# SCH_music-pad_2026-02-09.net
KiCad netlist of a schematic drawn in EasyEDA
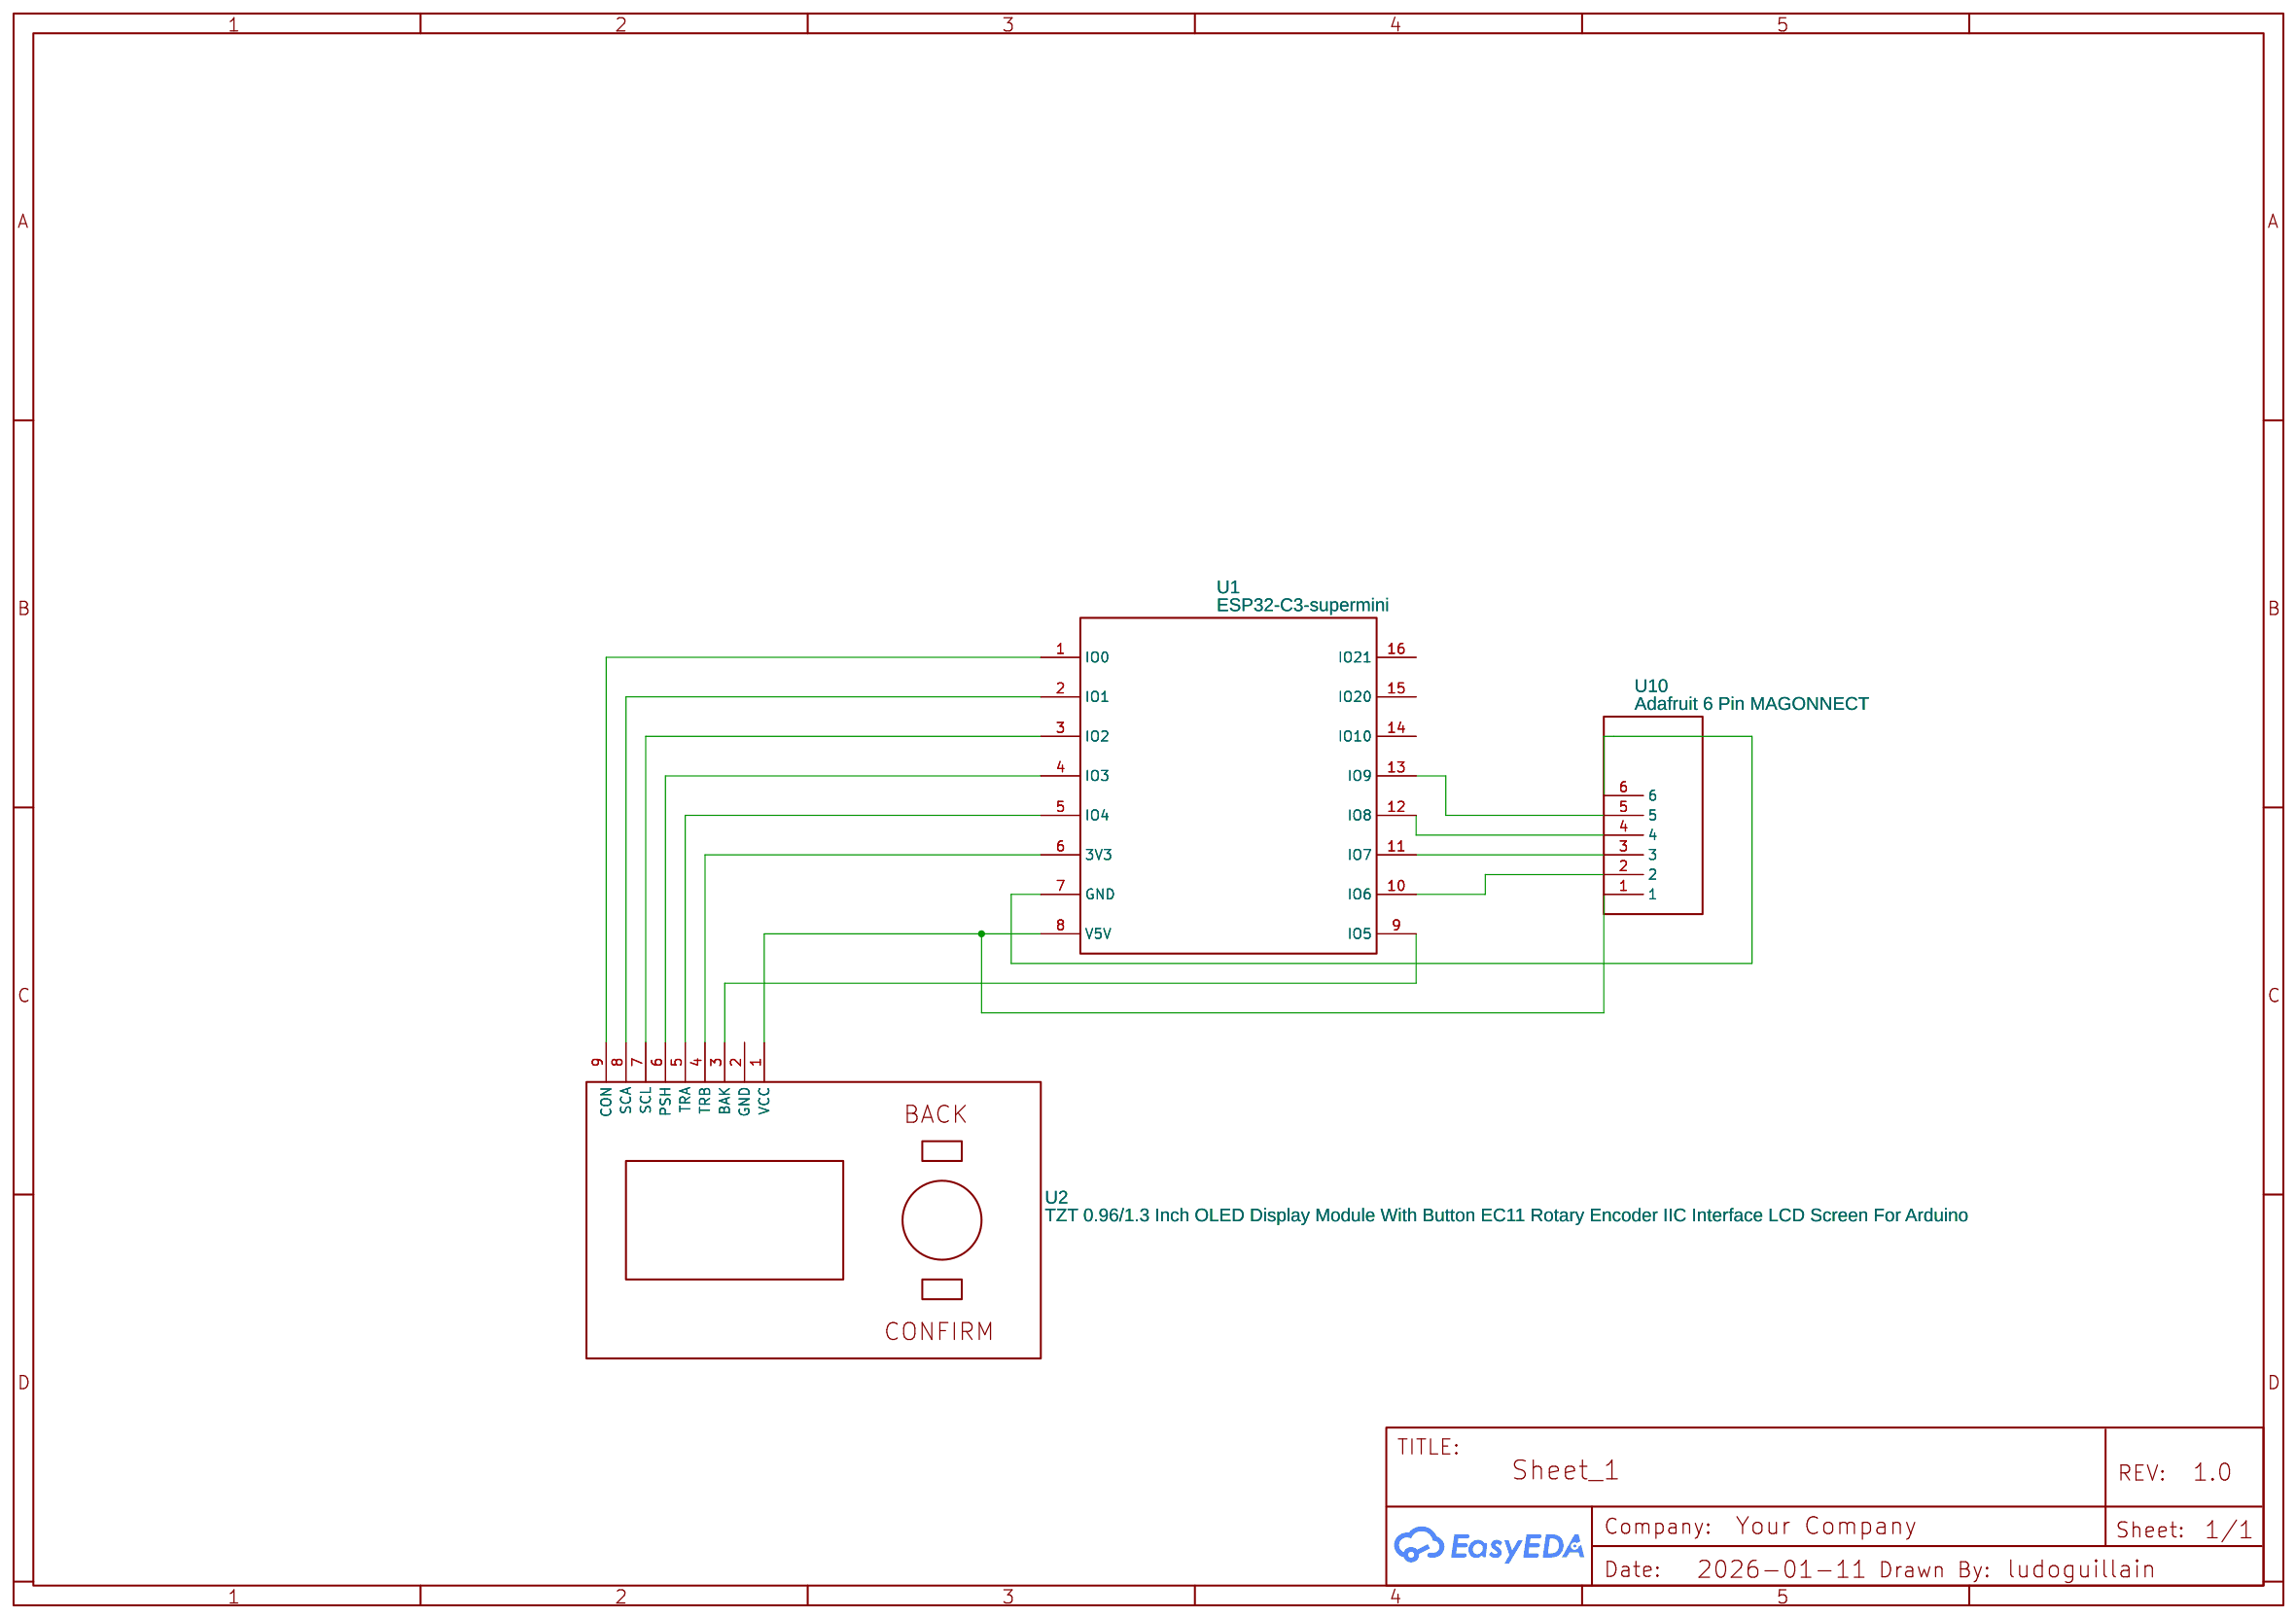
[diagram p0: schematic sheet]

(export (version "E")
  (design (tool "Eeschema 10.0.6"))
  (components
    (comp (ref "U1") (value "ESP32-C3-supermini") (libsource (lib "") (part "ESP32-C3-supermini")))
    (comp (ref "U2")
      (value "TZT 0.96/1.3 Inch OLED Display Module With Button EC11 Rotary Encoder IIC Interface LCD Screen For Arduino")
      (fields (field (name "Manufacturer Part") "8256") (field (name "Manufacturer") "TZT"))
      (libsource (lib "") (part "TZT 0.96/1.3 Inch OLED Display Module With Button EC11 Rotary Encoder IIC Interface LCD Screen For Arduino"))
    )
    (comp (ref "U10")
      (value "Adafruit 6 Pin MAGONNECT")
      (libsource (lib "") (part "Adafruit 6 Pin MAGONNECT"))
    )
  )
  (nets
    (net (code "1") (name "Net-(U1-3V3)") (class "Default")
      (node (ref "U1") (pin "6") (pinfunction "3V3_6") (pintype "unspecified"))
      (node (ref "U2") (pin "4") (pinfunction "TRB_4") (pintype "output"))
    )
    (net (code "2") (name "Net-(U1-GND)") (class "Default")
      (node (ref "U1") (pin "7") (pinfunction "GND_7") (pintype "unspecified"))
      (node (ref "U10") (pin "6") (pinfunction "6_6") (pintype "unspecified"))
    )
    (net (code "3") (name "Net-(U1-IO0)") (class "Default")
      (node (ref "U1") (pin "1") (pinfunction "IO0_1") (pintype "unspecified"))
      (node (ref "U2") (pin "9") (pinfunction "CON_9") (pintype "output"))
    )
    (net (code "4") (name "Net-(U1-IO1)") (class "Default")
      (node (ref "U1") (pin "2") (pinfunction "IO1_2") (pintype "unspecified"))
      (node (ref "U2") (pin "8") (pinfunction "SCA_8") (pintype "bidirectional"))
    )
    (net (code "5") (name "Net-(U1-IO2)") (class "Default")
      (node (ref "U1") (pin "3") (pinfunction "IO2_3") (pintype "unspecified"))
      (node (ref "U2") (pin "7") (pinfunction "SCL_7") (pintype "bidirectional"))
    )
    (net (code "6") (name "Net-(U1-IO3)") (class "Default")
      (node (ref "U1") (pin "4") (pinfunction "IO3_4") (pintype "unspecified"))
      (node (ref "U2") (pin "6") (pinfunction "PSH_6") (pintype "output"))
    )
    (net (code "7") (name "Net-(U1-IO4)") (class "Default")
      (node (ref "U1") (pin "5") (pinfunction "IO4_5") (pintype "unspecified"))
      (node (ref "U2") (pin "5") (pinfunction "TRA_5") (pintype "output"))
    )
    (net (code "8") (name "Net-(U1-IO5)") (class "Default")
      (node (ref "U1") (pin "9") (pinfunction "IO5_9") (pintype "unspecified"))
      (node (ref "U2") (pin "3") (pinfunction "BAK_3") (pintype "output"))
    )
    (net (code "9") (name "Net-(U1-IO6)") (class "Default")
      (node (ref "U1") (pin "10") (pinfunction "IO6_10") (pintype "unspecified"))
      (node (ref "U10") (pin "2") (pinfunction "2_2") (pintype "unspecified"))
    )
    (net (code "10") (name "Net-(U1-IO7)") (class "Default")
      (node (ref "U1") (pin "11") (pinfunction "IO7_11") (pintype "unspecified"))
      (node (ref "U10") (pin "3") (pinfunction "3_3") (pintype "unspecified"))
    )
    (net (code "11") (name "Net-(U1-IO8)") (class "Default")
      (node (ref "U1") (pin "12") (pinfunction "IO8_12") (pintype "unspecified"))
      (node (ref "U10") (pin "4") (pinfunction "4_4") (pintype "unspecified"))
    )
    (net (code "12") (name "Net-(U1-IO9)") (class "Default")
      (node (ref "U1") (pin "13") (pinfunction "IO9_13") (pintype "unspecified"))
      (node (ref "U10") (pin "5") (pinfunction "5_5") (pintype "unspecified"))
    )
    (net (code "13") (name "Net-(U1-V5V)") (class "Default")
      (node (ref "U1") (pin "8") (pinfunction "V5V_8") (pintype "unspecified"))
      (node (ref "U10") (pin "1") (pinfunction "1_1") (pintype "unspecified"))
      (node (ref "U2") (pin "1") (pinfunction "VCC_1") (pintype "passive"))
    )
    (net (code "14") (name "unconnected-(U1-IO10-Pad14)") (class "Default")
      (node (ref "U1") (pin "14") (pinfunction "IO10_14") (pintype "unspecified"))
    )
    (net (code "15") (name "unconnected-(U1-IO20-Pad15)") (class "Default")
      (node (ref "U1") (pin "15") (pinfunction "IO20_15") (pintype "unspecified"))
    )
    (net (code "16") (name "unconnected-(U1-IO21-Pad16)") (class "Default")
      (node (ref "U1") (pin "16") (pinfunction "IO21_16") (pintype "unspecified"))
    )
    (net (code "17") (name "unconnected-(U2-GND-Pad2)") (class "Default")
      (node (ref "U2") (pin "2") (pinfunction "GND_2") (pintype "passive"))
    )
  )
)
